# Macro_Duino.net
KiCad netlist of a schematic drawn in EAGLE
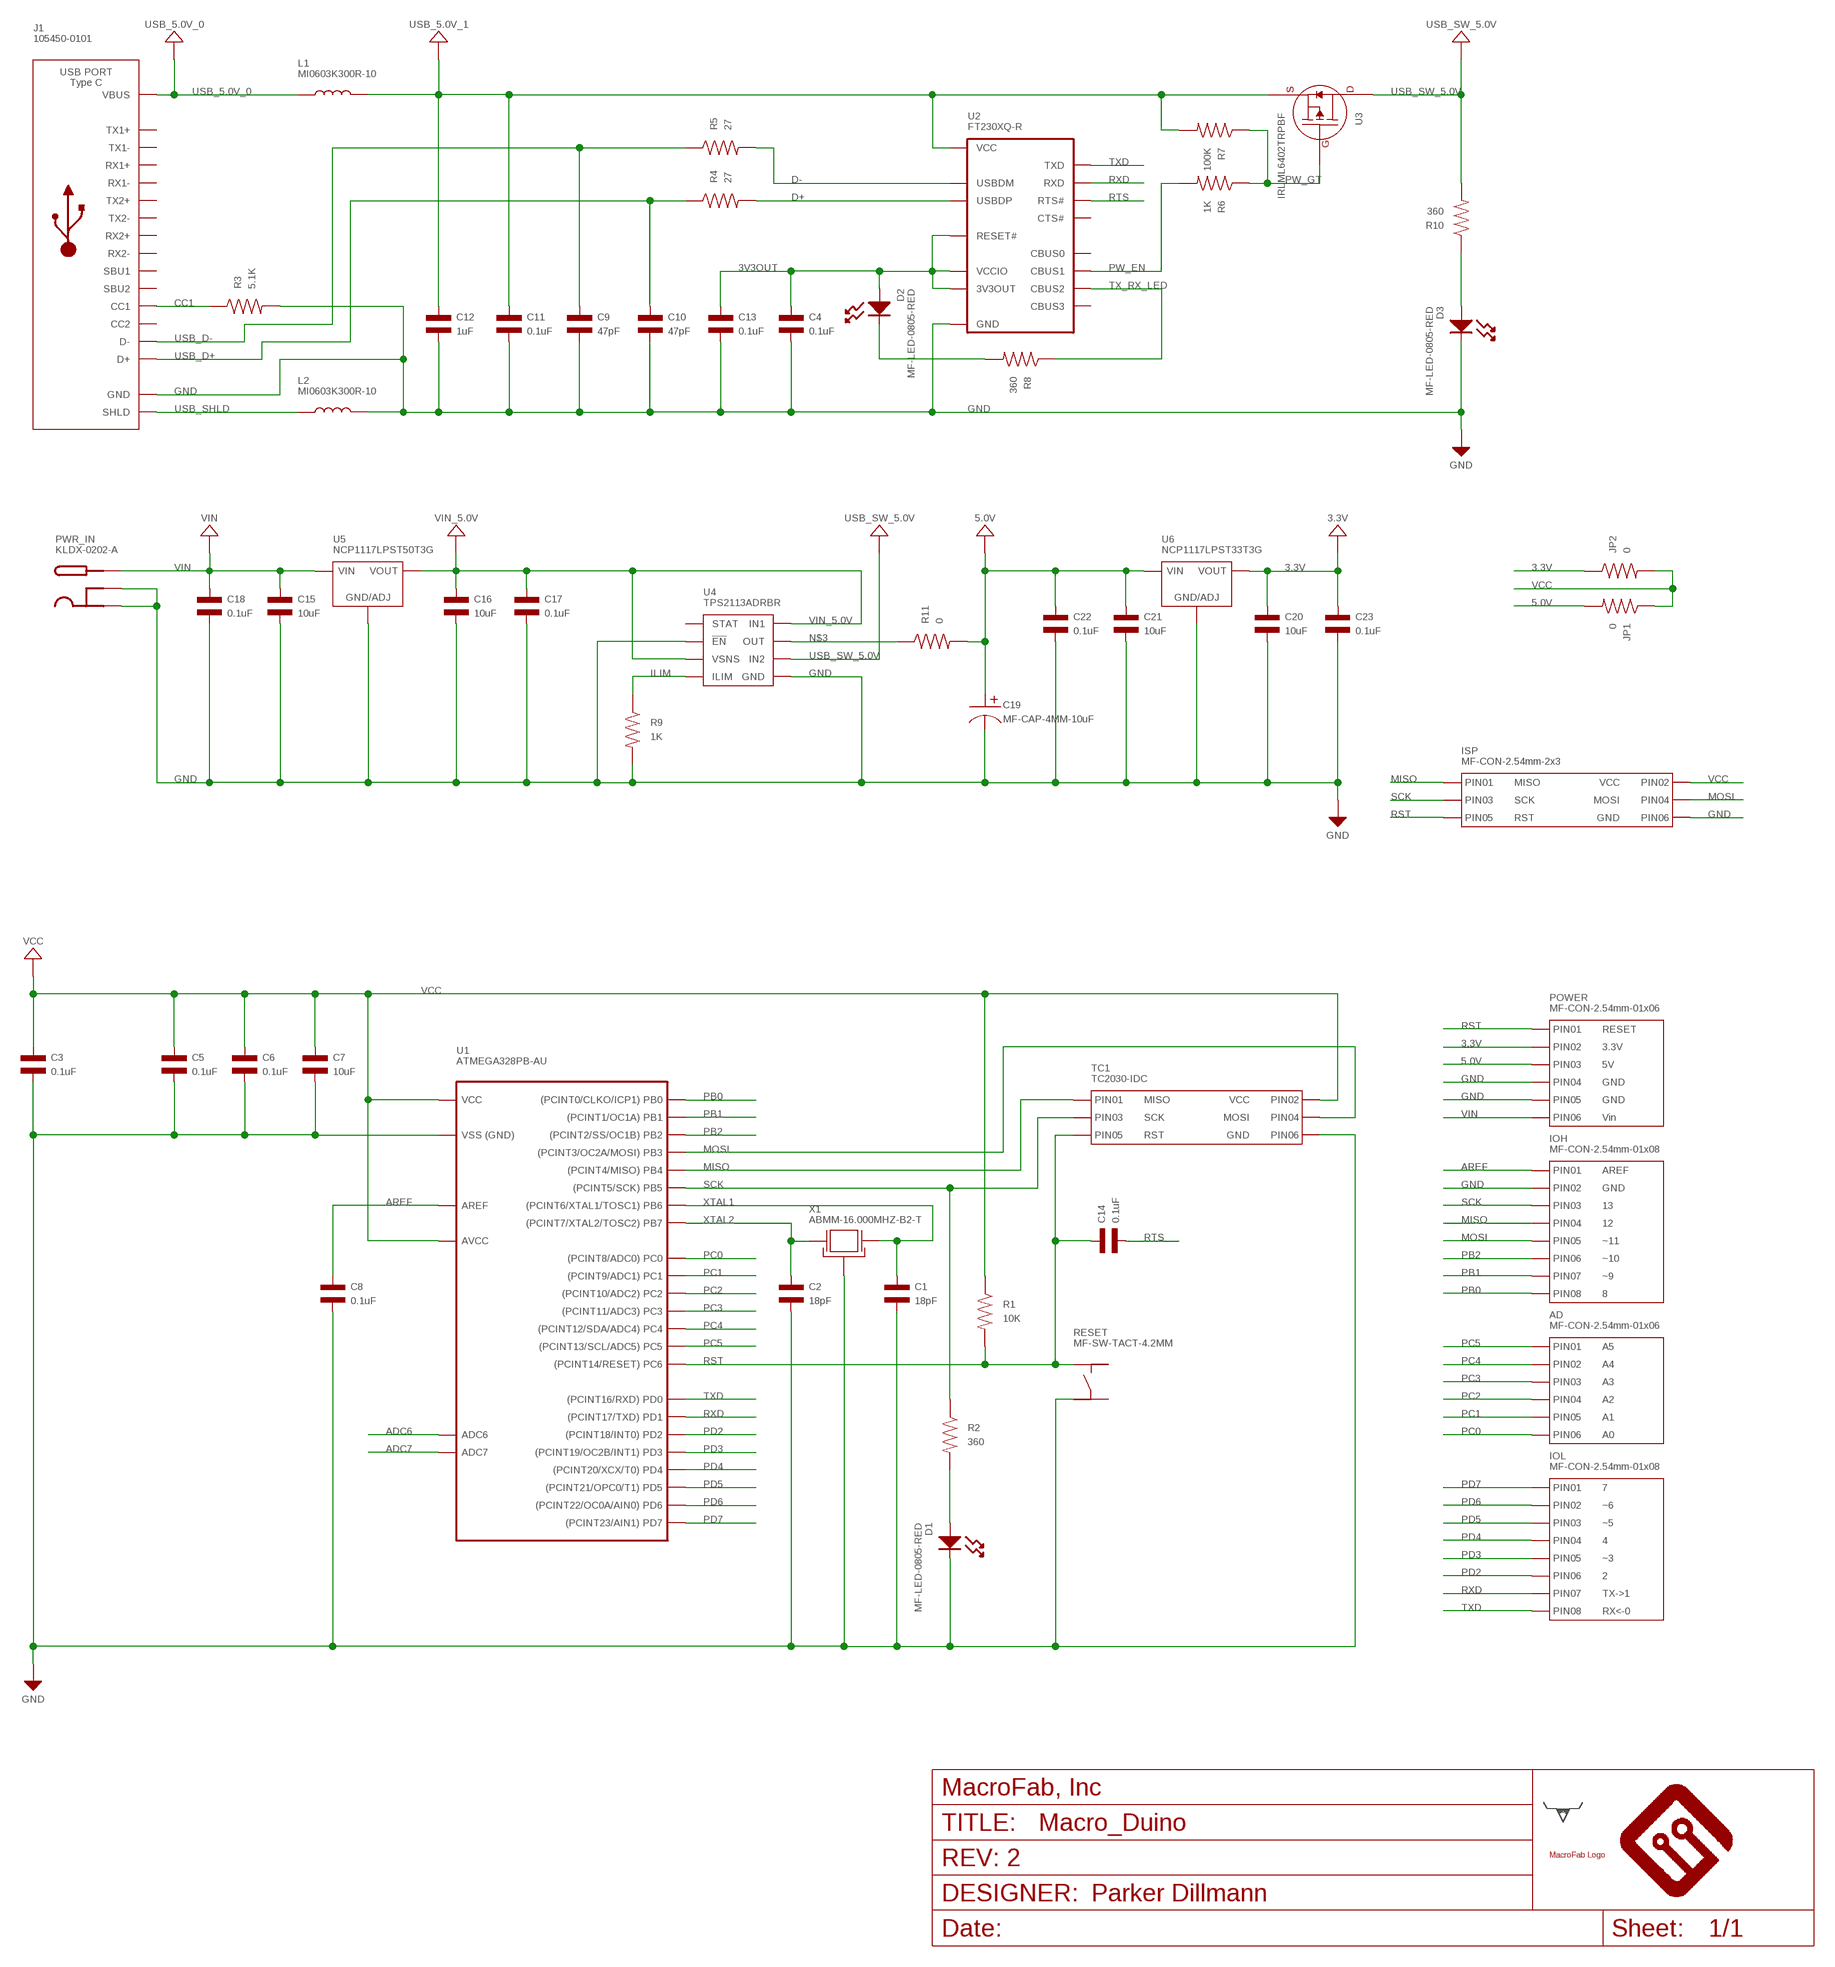
[diagram p0: schematic, sheet 1]

(export (version "E")
  (design (tool "Eeschema 10.0.6"))
  (components
    (comp (ref "AD")
      (value "MF-CON-2.54mm-01x06")
      (footprint "eagle-import:PTH_2.54MM_01X06")
      (fields
        (field (name "HOUSEPART") "YES")
        (field (name "LABEL01") "A5")
        (field (name "LABEL02") "A4")
        (field (name "LABEL03") "A3")
        (field (name "LABEL04") "A2")
        (field (name "LABEL05") "A1")
        (field (name "LABEL06") "A0")
      )
      (libsource (lib "eagle-import") (part "CON_01X06_PTH_2.54MM"))
    )
    (comp (ref "C1")
      (value "18pF")
      (footprint "eagle-import:C0603")
      (fields (field (name "MPN") "VJ0603A180JXACW1BC"))
      (libsource (lib "eagle-import") (part "CAPACITOR_NP_0603"))
    )
    (comp (ref "C2")
      (value "18pF")
      (footprint "eagle-import:C0603")
      (fields (field (name "MPN") "VJ0603A180JXACW1BC"))
      (libsource (lib "eagle-import") (part "CAPACITOR_NP_0603"))
    )
    (comp (ref "C3")
      (value "0.1uF")
      (footprint "eagle-import:C0603")
      (fields (field (name "MPN") "MF-CAP-0603-0.1uF"))
      (libsource (lib "eagle-import") (part "CAPACITOR_NP_0603"))
    )
    (comp (ref "C4")
      (value "0.1uF")
      (footprint "eagle-import:C0603")
      (fields (field (name "MPN") "MF-CAP-0603-0.1uF"))
      (libsource (lib "eagle-import") (part "CAPACITOR_NP_0603"))
    )
    (comp (ref "C5")
      (value "0.1uF")
      (footprint "eagle-import:C0603")
      (fields (field (name "MPN") "MF-CAP-0603-0.1uF"))
      (libsource (lib "eagle-import") (part "CAPACITOR_NP_0603"))
    )
    (comp (ref "C6")
      (value "0.1uF")
      (footprint "eagle-import:C0603")
      (fields (field (name "MPN") "MF-CAP-0603-0.1uF"))
      (libsource (lib "eagle-import") (part "CAPACITOR_NP_0603"))
    )
    (comp (ref "C7")
      (value "10uF")
      (footprint "eagle-import:C1206")
      (fields (field (name "MPN") "MF-CAP-1206-10uF"))
      (libsource (lib "eagle-import") (part "CAPACITOR_NP_1206"))
    )
    (comp (ref "C8")
      (value "0.1uF")
      (footprint "eagle-import:C0603")
      (fields (field (name "MPN") "MF-CAP-0603-0.1uF"))
      (libsource (lib "eagle-import") (part "CAPACITOR_NP_0603"))
    )
    (comp (ref "C9")
      (value "47pF")
      (footprint "eagle-import:C0603")
      (fields (field (name "MPN") "06035A470JAT2A"))
      (libsource (lib "eagle-import") (part "CAPACITOR_NP_0603"))
    )
    (comp (ref "C10")
      (value "47pF")
      (footprint "eagle-import:C0603")
      (fields (field (name "MPN") "06035A470JAT2A"))
      (libsource (lib "eagle-import") (part "CAPACITOR_NP_0603"))
    )
    (comp (ref "C11")
      (value "0.1uF")
      (footprint "eagle-import:C0603")
      (fields (field (name "MPN") "MF-CAP-0603-0.1uF"))
      (libsource (lib "eagle-import") (part "CAPACITOR_NP_0603"))
    )
    (comp (ref "C12")
      (value "1uF")
      (footprint "eagle-import:C0603")
      (fields (field (name "MPN") "MF-CAP-0603-1uF"))
      (libsource (lib "eagle-import") (part "CAPACITOR_NP_0603"))
    )
    (comp (ref "C13")
      (value "0.1uF")
      (footprint "eagle-import:C0603")
      (fields (field (name "MPN") "MF-CAP-0603-0.1uF"))
      (libsource (lib "eagle-import") (part "CAPACITOR_NP_0603"))
    )
    (comp (ref "C14")
      (value "0.1uF")
      (footprint "eagle-import:C0603")
      (fields (field (name "MPN") "MF-CAP-0603-0.1uF"))
      (libsource (lib "eagle-import") (part "CAPACITOR_NP_0603"))
    )
    (comp (ref "C15")
      (value "10uF")
      (footprint "eagle-import:C1206")
      (fields (field (name "MPN") "MF-CAP-1206-10uF"))
      (libsource (lib "eagle-import") (part "CAPACITOR_NP_1206"))
    )
    (comp (ref "C16")
      (value "10uF")
      (footprint "eagle-import:C1206")
      (fields (field (name "MPN") "MF-CAP-1206-10uF"))
      (libsource (lib "eagle-import") (part "CAPACITOR_NP_1206"))
    )
    (comp (ref "C17")
      (value "0.1uF")
      (footprint "eagle-import:C0603")
      (fields (field (name "MPN") "MF-CAP-0603-0.1uF"))
      (libsource (lib "eagle-import") (part "CAPACITOR_NP_0603"))
    )
    (comp (ref "C18")
      (value "0.1uF")
      (footprint "eagle-import:C0603")
      (fields (field (name "MPN") "MF-CAP-0603-0.1uF"))
      (libsource (lib "eagle-import") (part "CAPACITOR_NP_0603"))
    )
    (comp (ref "C19")
      (value "MF-CAP-4MM-10uF")
      (footprint "eagle-import:CP4MM")
      (fields (field (name "MPN") "MF-CAP-4MM-10uF"))
      (libsource (lib "eagle-import") (part "CAPACITOR_P_4MM"))
    )
    (comp (ref "C20")
      (value "10uF")
      (footprint "eagle-import:C1206")
      (fields (field (name "MPN") "MF-CAP-1206-10uF"))
      (libsource (lib "eagle-import") (part "CAPACITOR_NP_1206"))
    )
    (comp (ref "C21")
      (value "10uF")
      (footprint "eagle-import:C1206")
      (fields (field (name "MPN") "MF-CAP-1206-10uF"))
      (libsource (lib "eagle-import") (part "CAPACITOR_NP_1206"))
    )
    (comp (ref "C22")
      (value "0.1uF")
      (footprint "eagle-import:C0603")
      (fields (field (name "MPN") "MF-CAP-0603-0.1uF"))
      (libsource (lib "eagle-import") (part "CAPACITOR_NP_0603"))
    )
    (comp (ref "C23")
      (value "0.1uF")
      (footprint "eagle-import:C0603")
      (fields (field (name "MPN") "MF-CAP-0603-0.1uF"))
      (libsource (lib "eagle-import") (part "CAPACITOR_NP_0603"))
    )
    (comp (ref "D1")
      (value "MF-LED-0805-RED")
      (footprint "eagle-import:LED0805")
      (fields (field (name "HOUSEPART") "YES"))
      (libsource (lib "eagle-import") (part "LED_SINGLE-0805-RED"))
    )
    (comp (ref "D2")
      (value "MF-LED-0805-RED")
      (footprint "eagle-import:LED0805")
      (fields (field (name "HOUSEPART") "YES"))
      (libsource (lib "eagle-import") (part "LED_SINGLE-0805-RED"))
    )
    (comp (ref "D3")
      (value "MF-LED-0805-RED")
      (footprint "eagle-import:LED0805")
      (fields (field (name "HOUSEPART") "YES"))
      (libsource (lib "eagle-import") (part "LED_SINGLE-0805-RED"))
    )
    (comp (ref "FRAME1")
      (value "MF_FRAMEDEFAULT")
      (footprint "eagle-import:MF_FRAME_DEFAULT")
      (fields
        (field (name "HOUSEPART") "0")
        (field (name "DNAME") "Parker Dillmann")
        (field (name "REVNUM") "REV: 2")
      )
      (libsource (lib "eagle-import") (part "MF_FRAMEDEFAULT"))
    )
    (comp (ref "IOH")
      (value "MF-CON-2.54mm-01x08")
      (footprint "eagle-import:PTH_2.54MM_01X08")
      (fields
        (field (name "HOUSEPART") "YES")
        (field (name "LABEL01") "AREF")
        (field (name "LABEL02") "GND")
        (field (name "LABEL03") "13")
        (field (name "LABEL04") "12")
        (field (name "LABEL05") "~11")
        (field (name "LABEL06") "~10")
        (field (name "LABEL07") "~9")
        (field (name "LABEL08") "8")
      )
      (libsource (lib "eagle-import") (part "CON_01X08_PTH_2.54MM"))
    )
    (comp (ref "IOL")
      (value "MF-CON-2.54mm-01x08")
      (footprint "eagle-import:PTH_2.54MM_01X08")
      (fields
        (field (name "HOUSEPART") "YES")
        (field (name "LABEL01") "7")
        (field (name "LABEL02") "~6")
        (field (name "LABEL03") "~5")
        (field (name "LABEL04") "4")
        (field (name "LABEL05") "~3")
        (field (name "LABEL06") "2")
        (field (name "LABEL07") "TX->1")
        (field (name "LABEL08") "RX<-0")
      )
      (libsource (lib "eagle-import") (part "CON_01X08_PTH_2.54MM"))
    )
    (comp (ref "ISP")
      (value "MF-CON-2.54mm-2x3")
      (footprint "eagle-import:PTH_2.54MM_02X03")
      (fields
        (field (name "HOUSEPART") "YES")
        (field (name "LABEL01") "MISO")
        (field (name "LABEL02") "VCC")
        (field (name "LABEL03") "SCK")
        (field (name "LABEL04") "MOSI")
        (field (name "LABEL05") "RST")
        (field (name "LABEL06") "GND")
      )
      (libsource (lib "eagle-import") (part "CON_02X03_PTH_2.54MM"))
    )
    (comp (ref "J1")
      (value "105450-0101")
      (footprint "eagle-import:105450-0101")
      (fields (field (name "MPN") "105450-0101"))
      (libsource (lib "eagle-import") (part "USB_TYPE-C_105450-0101"))
    )
    (comp (ref "JP1")
      (value "0")
      (footprint "eagle-import:R0805")
      (fields (field (name "MPN") "MF-RES-0805-0"))
      (libsource (lib "eagle-import") (part "RESISTOR_0805"))
    )
    (comp (ref "JP2")
      (value "0")
      (footprint "eagle-import:R0805")
      (fields (field (name "MPN") "MF-RES-0805-0") (field (name "POPULATE") "0"))
      (libsource (lib "eagle-import") (part "RESISTOR_0805"))
    )
    (comp (ref "L1")
      (value "MI0603K300R-10")
      (footprint "eagle-import:L0603")
      (fields (field (name "MPN") "MI0603K300R-10"))
      (libsource (lib "eagle-import") (part "INDUCTOR_0603"))
    )
    (comp (ref "L2")
      (value "MI0603K300R-10")
      (footprint "eagle-import:L0603")
      (fields (field (name "MPN") "MI0603K300R-10"))
      (libsource (lib "eagle-import") (part "INDUCTOR_0603"))
    )
    (comp (ref "POWER")
      (value "MF-CON-2.54mm-01x06")
      (footprint "eagle-import:PTH_2.54MM_01X06")
      (fields
        (field (name "HOUSEPART") "YES")
        (field (name "LABEL01") "RESET")
        (field (name "LABEL02") "3.3V")
        (field (name "LABEL03") "5V")
        (field (name "LABEL04") "GND")
        (field (name "LABEL05") "GND")
        (field (name "LABEL06") "Vin")
      )
      (libsource (lib "eagle-import") (part "CON_01X06_PTH_2.54MM"))
    )
    (comp (ref "PWR_IN")
      (value "KLDX-0202-A")
      (footprint "eagle-import:DC_PWR_JACK")
      (fields (field (name "HOUSEPART") "NO"))
      (libsource (lib "eagle-import") (part "DC_PWR_JACK_2.0MM_RIGHT"))
    )
    (comp (ref "R1")
      (value "10K")
      (footprint "eagle-import:R0603")
      (fields (field (name "MPN") "MF-RES-0603-10K"))
      (libsource (lib "eagle-import") (part "RESISTOR_0603"))
    )
    (comp (ref "R2")
      (value "360")
      (footprint "eagle-import:R0603")
      (fields (field (name "MPN") "MF-RES-0603-360"))
      (libsource (lib "eagle-import") (part "RESISTOR_0603"))
    )
    (comp (ref "R3")
      (value "5.1K")
      (footprint "eagle-import:R0603")
      (fields (field (name "MPN") "CR0603-FX-5101ELF"))
      (libsource (lib "eagle-import") (part "RESISTOR_0603"))
    )
    (comp (ref "R4")
      (value "27")
      (footprint "eagle-import:R0603")
      (fields (field (name "MPN") "MF-RES-0603-27"))
      (libsource (lib "eagle-import") (part "RESISTOR_0603"))
    )
    (comp (ref "R5")
      (value "27")
      (footprint "eagle-import:R0603")
      (fields (field (name "MPN") "MF-RES-0603-27"))
      (libsource (lib "eagle-import") (part "RESISTOR_0603"))
    )
    (comp (ref "R6")
      (value "1K")
      (footprint "eagle-import:R0603")
      (fields (field (name "MPN") "MF-RES-0603-1K"))
      (libsource (lib "eagle-import") (part "RESISTOR_0603"))
    )
    (comp (ref "R7")
      (value "100K")
      (footprint "eagle-import:R0603")
      (fields (field (name "MPN") "MF-RES-0603-100K"))
      (libsource (lib "eagle-import") (part "RESISTOR_0603"))
    )
    (comp (ref "R8")
      (value "360")
      (footprint "eagle-import:R0603")
      (fields (field (name "MPN") "MF-RES-0603-360"))
      (libsource (lib "eagle-import") (part "RESISTOR_0603"))
    )
    (comp (ref "R9")
      (value "1K")
      (footprint "eagle-import:R0603")
      (fields (field (name "MPN") "MF-RES-0603-1K"))
      (libsource (lib "eagle-import") (part "RESISTOR_0603"))
    )
    (comp (ref "R10")
      (value "360")
      (footprint "eagle-import:R0603")
      (fields (field (name "MPN") "MF-RES-0603-360"))
      (libsource (lib "eagle-import") (part "RESISTOR_0603"))
    )
    (comp (ref "R11")
      (value "0")
      (footprint "eagle-import:R0805")
      (fields (field (name "MPN") "MF-RES-0805-0"))
      (libsource (lib "eagle-import") (part "RESISTOR_0805"))
    )
    (comp (ref "RESET")
      (value "MF-SW-TACT-4.2MM")
      (footprint "eagle-import:TACT4.2MM")
      (fields (field (name "HOUSEPART") "YES"))
      (libsource (lib "eagle-import") (part "TACT_4.2MM"))
    )
    (comp (ref "TC1")
      (value "TC2030-IDC")
      (footprint "eagle-import:TC2030-IDC-FP")
      (fields (field (name "HOUSEPART") "NO"))
      (libsource (lib "eagle-import") (part "CON_02X03_TC2030-IDC_AVRISP"))
    )
    (comp (ref "U$14")
      (value "MF_LOGOLOGO")
      (footprint "eagle-import:MF_LOGO")
      (libsource (lib "eagle-import") (part "MF_LOGOLOGO"))
    )
    (comp (ref "U$15")
      (value "LHE_LOGOLHE_LOGO")
      (footprint "eagle-import:LHE_LOGO")
      (libsource (lib "eagle-import") (part "LHE_LOGOLHE_LOGO"))
    )
    (comp (ref "U1")
      (value "ATMEGA328PB-AU")
      (footprint "eagle-import:TQFP32")
      (fields
        (field (name "HOUSEPART") "NO")
        (field (name "MPN") "ATMEGA328P-AU")
        (field (name "MPN_1") "ATMEGA328PB-AU ")
      )
      (libsource (lib "eagle-import") (part "ATMEGA328P-AU"))
    )
    (comp (ref "U2")
      (value "FT230XQ-R")
      (footprint "eagle-import:FT230X_QFN-16")
      (libsource (lib "eagle-import") (part "FT230XQ"))
    )
    (comp (ref "U3")
      (value "IRLML6402TRPBF")
      (footprint "eagle-import:SOT-23-3")
      (libsource (lib "eagle-import") (part "MOSFET_P-CHANNEL_SINGLE_SOT-23"))
    )
    (comp (ref "U4")
      (value "TPS2113ADRBR")
      (footprint "eagle-import:TPS211X_SON-8")
      (libsource (lib "eagle-import") (part "TPS211(2/3)ADR"))
    )
    (comp (ref "U5")
      (value "NCP1117LPST50T3G")
      (footprint "eagle-import:SOT-223-3")
      (fields (field (name "HOUSEPART") "NO"))
      (libsource (lib "eagle-import") (part "NCP1117LPST50T3G"))
    )
    (comp (ref "U6")
      (value "NCP1117LPST33T3G")
      (footprint "eagle-import:SOT-223-3")
      (fields (field (name "HOUSEPART") "NO"))
      (libsource (lib "eagle-import") (part "NCP1117LPST33T3G"))
    )
    (comp (ref "X1")
      (value "ABMM-16.000MHZ-B2-T")
      (footprint "eagle-import:7MMX5MM")
      (fields (field (name "HOUSEPART") "NO") (field (name "MPN") "ABMM-16.000MHZ-B2-T"))
      (libsource (lib "eagle-import") (part "CYRSTAL_GND_ABMM"))
    )
  )
  (nets
    (net (code "1") (name "/3V3OUT") (class "Default")
      (node (ref "C13") (pin "P$1") (pinfunction "P$1_P$1") (pintype "passive"))
      (node (ref "C4") (pin "P$1") (pinfunction "P$1_P$1") (pintype "passive"))
      (node (ref "D2") (pin "ANODE") (pinfunction "ANODE_ANODE") (pintype "power_in"))
      (node (ref "U2") (pin "1") (pinfunction "VCCIO_1") (pintype "bidirectional"))
      (node (ref "U2") (pin "8") (pinfunction "3V3OUT_8") (pintype "bidirectional"))
      (node (ref "U2") (pin "9") (pinfunction "RESET#_9") (pintype "bidirectional"))
    )
    (net (code "2") (name "/ADC6") (class "Default")
      (node (ref "U1") (pin "P$19") (pinfunction "ADC6_P$19") (pintype "bidirectional"))
    )
    (net (code "3") (name "/ADC7") (class "Default")
      (node (ref "U1") (pin "P$22") (pinfunction "ADC7_P$22") (pintype "bidirectional"))
    )
    (net (code "4") (name "/AREF") (class "Default")
      (node (ref "C8") (pin "P$1") (pinfunction "P$1_P$1") (pintype "passive"))
      (node (ref "IOH") (pin "P$1") (pinfunction "PIN1_P$1") (pintype "bidirectional"))
      (node (ref "U1") (pin "P$20") (pinfunction "AREF_P$20") (pintype "power_in"))
    )
    (net (code "5") (name "/CC1") (class "Default")
      (node (ref "J1") (pin "A5") (pinfunction "CC1_A5") (pintype "bidirectional"))
      (node (ref "R3") (pin "P$1") (pinfunction "P$1_P$1") (pintype "passive"))
    )
    (net (code "6") (name "/D+") (class "Default")
      (node (ref "R4") (pin "P$2") (pinfunction "P$2_P$2") (pintype "passive"))
      (node (ref "U2") (pin "6") (pinfunction "USBDP_6") (pintype "bidirectional"))
    )
    (net (code "7") (name "/D-") (class "Default")
      (node (ref "R5") (pin "P$2") (pinfunction "P$2_P$2") (pintype "passive"))
      (node (ref "U2") (pin "7") (pinfunction "USBDM_7") (pintype "bidirectional"))
    )
    (net (code "8") (name "/ILIM") (class "Default")
      (node (ref "R9") (pin "P$1") (pinfunction "P$1_P$1") (pintype "passive"))
      (node (ref "U4") (pin "4") (pinfunction "ILIM_4") (pintype "bidirectional"))
    )
    (net (code "9") (name "/MISO") (class "Default")
      (node (ref "IOH") (pin "P$4") (pinfunction "PIN4_P$4") (pintype "bidirectional"))
      (node (ref "ISP") (pin "P$1") (pinfunction "PIN1_P$1") (pintype "bidirectional"))
      (node (ref "TC1") (pin "P$1") (pinfunction "PIN1_P$1") (pintype "bidirectional"))
      (node (ref "U1") (pin "P$16") (pinfunction "PB4_P$16") (pintype "bidirectional"))
    )
    (net (code "10") (name "/MOSI") (class "Default")
      (node (ref "IOH") (pin "P$5") (pinfunction "PIN5_P$5") (pintype "bidirectional"))
      (node (ref "ISP") (pin "P$4") (pinfunction "PIN4_P$4") (pintype "bidirectional"))
      (node (ref "TC1") (pin "P$4") (pinfunction "PIN4_P$4") (pintype "bidirectional"))
      (node (ref "U1") (pin "P$15") (pinfunction "PB3_P$15") (pintype "bidirectional"))
    )
    (net (code "11") (name "/N$3") (class "Default")
      (node (ref "R11") (pin "P$1") (pinfunction "P$1_P$1") (pintype "passive"))
      (node (ref "U4") (pin "7") (pinfunction "OUT_7") (pintype "bidirectional"))
    )
    (net (code "12") (name "/PB0") (class "Default")
      (node (ref "IOH") (pin "P$8") (pinfunction "PIN8_P$8") (pintype "bidirectional"))
      (node (ref "U1") (pin "P$12") (pinfunction "PB0_P$12") (pintype "bidirectional"))
    )
    (net (code "13") (name "/PB1") (class "Default")
      (node (ref "IOH") (pin "P$7") (pinfunction "PIN7_P$7") (pintype "bidirectional"))
      (node (ref "U1") (pin "P$13") (pinfunction "PB1_P$13") (pintype "bidirectional"))
    )
    (net (code "14") (name "/PB2") (class "Default")
      (node (ref "IOH") (pin "P$6") (pinfunction "PIN6_P$6") (pintype "bidirectional"))
      (node (ref "U1") (pin "P$14") (pinfunction "PB2_P$14") (pintype "bidirectional"))
    )
    (net (code "15") (name "/PC0") (class "Default")
      (node (ref "AD") (pin "P$6") (pinfunction "PIN6_P$6") (pintype "bidirectional"))
      (node (ref "U1") (pin "P$23") (pinfunction "PC0_P$23") (pintype "bidirectional"))
    )
    (net (code "16") (name "/PC1") (class "Default")
      (node (ref "AD") (pin "P$5") (pinfunction "PIN5_P$5") (pintype "bidirectional"))
      (node (ref "U1") (pin "P$24") (pinfunction "PC1_P$24") (pintype "bidirectional"))
    )
    (net (code "17") (name "/PC2") (class "Default")
      (node (ref "AD") (pin "P$4") (pinfunction "PIN4_P$4") (pintype "bidirectional"))
      (node (ref "U1") (pin "P$25") (pinfunction "PC2_P$25") (pintype "bidirectional"))
    )
    (net (code "18") (name "/PC3") (class "Default")
      (node (ref "AD") (pin "P$3") (pinfunction "PIN3_P$3") (pintype "bidirectional"))
      (node (ref "U1") (pin "P$26") (pinfunction "PC3_P$26") (pintype "bidirectional"))
    )
    (net (code "19") (name "/PC4") (class "Default")
      (node (ref "AD") (pin "P$2") (pinfunction "PIN2_P$2") (pintype "bidirectional"))
      (node (ref "U1") (pin "P$27") (pinfunction "PC4_P$27") (pintype "bidirectional"))
    )
    (net (code "20") (name "/PC5") (class "Default")
      (node (ref "AD") (pin "P$1") (pinfunction "PIN1_P$1") (pintype "bidirectional"))
      (node (ref "U1") (pin "P$28") (pinfunction "PC5_P$28") (pintype "bidirectional"))
    )
    (net (code "21") (name "/PD2") (class "Default")
      (node (ref "IOL") (pin "P$6") (pinfunction "PIN6_P$6") (pintype "bidirectional"))
      (node (ref "U1") (pin "P$32") (pinfunction "PD2_P$32") (pintype "bidirectional"))
    )
    (net (code "22") (name "/PD3") (class "Default")
      (node (ref "IOL") (pin "P$5") (pinfunction "PIN5_P$5") (pintype "bidirectional"))
      (node (ref "U1") (pin "P$1") (pinfunction "PD3_P$1") (pintype "bidirectional"))
    )
    (net (code "23") (name "/PD4") (class "Default")
      (node (ref "IOL") (pin "P$4") (pinfunction "PIN4_P$4") (pintype "bidirectional"))
      (node (ref "U1") (pin "P$2") (pinfunction "PD4_P$2") (pintype "bidirectional"))
    )
    (net (code "24") (name "/PD5") (class "Default")
      (node (ref "IOL") (pin "P$3") (pinfunction "PIN3_P$3") (pintype "bidirectional"))
      (node (ref "U1") (pin "P$9") (pinfunction "PD5_P$9") (pintype "bidirectional"))
    )
    (net (code "25") (name "/PD6") (class "Default")
      (node (ref "IOL") (pin "P$2") (pinfunction "PIN2_P$2") (pintype "bidirectional"))
      (node (ref "U1") (pin "P$10") (pinfunction "PD6_P$10") (pintype "bidirectional"))
    )
    (net (code "26") (name "/PD7") (class "Default")
      (node (ref "IOL") (pin "P$1") (pinfunction "PIN1_P$1") (pintype "bidirectional"))
      (node (ref "U1") (pin "P$11") (pinfunction "PD7_P$11") (pintype "bidirectional"))
    )
    (net (code "27") (name "/PW_EN") (class "Default")
      (node (ref "R6") (pin "P$2") (pinfunction "P$2_P$2") (pintype "passive"))
      (node (ref "U2") (pin "11") (pinfunction "CBUS1_11") (pintype "bidirectional"))
    )
    (net (code "28") (name "/PW_GT") (class "Default")
      (node (ref "R6") (pin "P$1") (pinfunction "P$1_P$1") (pintype "passive"))
      (node (ref "R7") (pin "P$1") (pinfunction "P$1_P$1") (pintype "passive"))
      (node (ref "U3") (pin "1") (pinfunction "GATE_1") (pintype "bidirectional"))
    )
    (net (code "29") (name "/RST") (class "Default")
      (node (ref "C14") (pin "P$1") (pinfunction "P$1_P$1") (pintype "passive"))
      (node (ref "ISP") (pin "P$5") (pinfunction "PIN5_P$5") (pintype "bidirectional"))
      (node (ref "POWER") (pin "P$1") (pinfunction "PIN1_P$1") (pintype "bidirectional"))
      (node (ref "R1") (pin "P$2") (pinfunction "P$2_P$2") (pintype "passive"))
      (node (ref "RESET") (pin "P$1") (pinfunction "P$1_P$1") (pintype "bidirectional"))
      (node (ref "TC1") (pin "P$5") (pinfunction "PIN5_P$5") (pintype "bidirectional"))
      (node (ref "U1") (pin "P$29") (pinfunction "PC6_P$29") (pintype "bidirectional"))
    )
    (net (code "30") (name "/RTS") (class "Default")
      (node (ref "C14") (pin "P$2") (pinfunction "P$2_P$2") (pintype "passive"))
      (node (ref "U2") (pin "16") (pinfunction "RTS#_16") (pintype "bidirectional"))
    )
    (net (code "31") (name "/RXD") (class "Default")
      (node (ref "IOL") (pin "P$7") (pinfunction "PIN7_P$7") (pintype "bidirectional"))
      (node (ref "U1") (pin "P$31") (pinfunction "PD1_P$31") (pintype "bidirectional"))
      (node (ref "U2") (pin "2") (pinfunction "RXD_2") (pintype "bidirectional"))
    )
    (net (code "32") (name "/SCK") (class "Default")
      (node (ref "IOH") (pin "P$3") (pinfunction "PIN3_P$3") (pintype "bidirectional"))
      (node (ref "ISP") (pin "P$3") (pinfunction "PIN3_P$3") (pintype "bidirectional"))
      (node (ref "R2") (pin "P$1") (pinfunction "P$1_P$1") (pintype "passive"))
      (node (ref "TC1") (pin "P$3") (pinfunction "PIN3_P$3") (pintype "bidirectional"))
      (node (ref "U1") (pin "P$17") (pinfunction "PB5_P$17") (pintype "bidirectional"))
    )
    (net (code "33") (name "/TXD") (class "Default")
      (node (ref "IOL") (pin "P$8") (pinfunction "PIN8_P$8") (pintype "bidirectional"))
      (node (ref "U1") (pin "P$30") (pinfunction "PD0_P$30") (pintype "bidirectional"))
      (node (ref "U2") (pin "15") (pinfunction "TXD_15") (pintype "bidirectional"))
    )
    (net (code "34") (name "/TX_RX_LED") (class "Default")
      (node (ref "R8") (pin "P$1") (pinfunction "P$1_P$1") (pintype "passive"))
      (node (ref "U2") (pin "5") (pinfunction "CBUS2_5") (pintype "bidirectional"))
    )
    (net (code "35") (name "/USB_D+") (class "Default")
      (node (ref "C10") (pin "P$1") (pinfunction "P$1_P$1") (pintype "passive"))
      (node (ref "J1") (pin "A6") (pinfunction "D+_A6") (pintype "bidirectional"))
      (node (ref "J1") (pin "B6") (pinfunction "D+_B6") (pintype "bidirectional"))
      (node (ref "R4") (pin "P$1") (pinfunction "P$1_P$1") (pintype "passive"))
    )
    (net (code "36") (name "/USB_D-") (class "Default")
      (node (ref "C9") (pin "P$1") (pinfunction "P$1_P$1") (pintype "passive"))
      (node (ref "J1") (pin "A7") (pinfunction "D-_A7") (pintype "bidirectional"))
      (node (ref "J1") (pin "B7") (pinfunction "D-_B7") (pintype "bidirectional"))
      (node (ref "R5") (pin "P$1") (pinfunction "P$1_P$1") (pintype "passive"))
    )
    (net (code "37") (name "/USB_SHLD") (class "Default")
      (node (ref "J1") (pin "S_T1") (pinfunction "SHLD_S_T1") (pintype "bidirectional"))
      (node (ref "J1") (pin "S_T2") (pinfunction "SHLD_S_T2") (pintype "bidirectional"))
      (node (ref "J1") (pin "S_T3") (pinfunction "SHLD_S_T3") (pintype "bidirectional"))
      (node (ref "J1") (pin "S_T4") (pinfunction "SHLD_S_T4") (pintype "bidirectional"))
      (node (ref "L2") (pin "P$1") (pinfunction "P$1_P$1") (pintype "passive"))
    )
    (net (code "38") (name "/XTAL1") (class "Default")
      (node (ref "C1") (pin "P$1") (pinfunction "P$1_P$1") (pintype "passive"))
      (node (ref "U1") (pin "P$7") (pinfunction "PB6_P$7") (pintype "bidirectional"))
      (node (ref "X1") (pin "P$3") (pinfunction "X1_P$3") (pintype "bidirectional"))
    )
    (net (code "39") (name "/XTAL2") (class "Default")
      (node (ref "C2") (pin "P$1") (pinfunction "P$1_P$1") (pintype "passive"))
      (node (ref "U1") (pin "P$8") (pinfunction "PB7_P$8") (pintype "bidirectional"))
      (node (ref "X1") (pin "P$1") (pinfunction "X0_P$1") (pintype "bidirectional"))
    )
    (net (code "40") (name "3.3V") (class "Default")
      (node (ref "C20") (pin "P$1") (pinfunction "P$1_P$1") (pintype "passive"))
      (node (ref "C23") (pin "P$1") (pinfunction "P$1_P$1") (pintype "passive"))
      (node (ref "JP2") (pin "P$1") (pinfunction "P$1_P$1") (pintype "passive"))
      (node (ref "POWER") (pin "P$2") (pinfunction "PIN2_P$2") (pintype "bidirectional"))
      (node (ref "U6") (pin "P$1") (pinfunction "VOUT_P$1") (pintype "bidirectional"))
      (node (ref "U6") (pin "P$3") (pinfunction "VOUT_P$3") (pintype "bidirectional"))
    )
    (net (code "41") (name "5.0V") (class "Default")
      (node (ref "C19") (pin "P$1") (pinfunction "P$1_P$1") (pintype "passive"))
      (node (ref "C21") (pin "P$1") (pinfunction "P$1_P$1") (pintype "passive"))
      (node (ref "C22") (pin "P$1") (pinfunction "P$1_P$1") (pintype "passive"))
      (node (ref "JP1") (pin "P$2") (pinfunction "P$2_P$2") (pintype "passive"))
      (node (ref "POWER") (pin "P$3") (pinfunction "PIN3_P$3") (pintype "bidirectional"))
      (node (ref "R11") (pin "P$2") (pinfunction "P$2_P$2") (pintype "passive"))
      (node (ref "U6") (pin "P$4") (pinfunction "VIN_P$4") (pintype "bidirectional"))
    )
    (net (code "42") (name "GND") (class "Default")
      (node (ref "C1") (pin "P$2") (pinfunction "P$2_P$2") (pintype "passive"))
      (node (ref "C10") (pin "P$2") (pinfunction "P$2_P$2") (pintype "passive"))
      (node (ref "C11") (pin "P$2") (pinfunction "P$2_P$2") (pintype "passive"))
      (node (ref "C12") (pin "P$2") (pinfunction "P$2_P$2") (pintype "passive"))
      (node (ref "C13") (pin "P$2") (pinfunction "P$2_P$2") (pintype "passive"))
      (node (ref "C15") (pin "P$2") (pinfunction "P$2_P$2") (pintype "passive"))
      (node (ref "C16") (pin "P$2") (pinfunction "P$2_P$2") (pintype "passive"))
      (node (ref "C17") (pin "P$2") (pinfunction "P$2_P$2") (pintype "passive"))
      (node (ref "C18") (pin "P$2") (pinfunction "P$2_P$2") (pintype "passive"))
      (node (ref "C19") (pin "P$2") (pinfunction "P$2_P$2") (pintype "passive"))
      (node (ref "C2") (pin "P$2") (pinfunction "P$2_P$2") (pintype "passive"))
      (node (ref "C20") (pin "P$2") (pinfunction "P$2_P$2") (pintype "passive"))
      (node (ref "C21") (pin "P$2") (pinfunction "P$2_P$2") (pintype "passive"))
      (node (ref "C22") (pin "P$2") (pinfunction "P$2_P$2") (pintype "passive"))
      (node (ref "C23") (pin "P$2") (pinfunction "P$2_P$2") (pintype "passive"))
      (node (ref "C3") (pin "P$2") (pinfunction "P$2_P$2") (pintype "passive"))
      (node (ref "C4") (pin "P$2") (pinfunction "P$2_P$2") (pintype "passive"))
      (node (ref "C5") (pin "P$2") (pinfunction "P$2_P$2") (pintype "passive"))
      (node (ref "C6") (pin "P$2") (pinfunction "P$2_P$2") (pintype "passive"))
      (node (ref "C7") (pin "P$2") (pinfunction "P$2_P$2") (pintype "passive"))
      (node (ref "C8") (pin "P$2") (pinfunction "P$2_P$2") (pintype "passive"))
      (node (ref "C9") (pin "P$2") (pinfunction "P$2_P$2") (pintype "passive"))
      (node (ref "D1") (pin "CATHODE") (pinfunction "CATHODE_CATHODE") (pintype "power_in"))
      (node (ref "D3") (pin "CATHODE") (pinfunction "CATHODE_CATHODE") (pintype "power_in"))
      (node (ref "IOH") (pin "P$2") (pinfunction "PIN2_P$2") (pintype "bidirectional"))
      (node (ref "ISP") (pin "P$6") (pinfunction "PIN6_P$6") (pintype "bidirectional"))
      (node (ref "J1") (pin "A1") (pinfunction "GND_A1") (pintype "bidirectional"))
      (node (ref "J1") (pin "A12") (pinfunction "GND_A12") (pintype "bidirectional"))
      (node (ref "J1") (pin "B1") (pinfunction "GND_B1") (pintype "bidirectional"))
      (node (ref "J1") (pin "B12") (pinfunction "GND_B12") (pintype "bidirectional"))
      (node (ref "L2") (pin "P$2") (pinfunction "P$2_P$2") (pintype "passive"))
      (node (ref "POWER") (pin "P$4") (pinfunction "PIN4_P$4") (pintype "bidirectional"))
      (node (ref "POWER") (pin "P$5") (pinfunction "PIN5_P$5") (pintype "bidirectional"))
      (node (ref "PWR_IN") (pin "SLEEVE1") (pinfunction "SLEEVE_SLEEVE1") (pintype "power_in"))
      (node (ref "PWR_IN") (pin "SLEEVE2") (pinfunction "SLEEVE_SHUNT_SLEEVE2") (pintype "power_in"))
      (node (ref "R3") (pin "P$2") (pinfunction "P$2_P$2") (pintype "passive"))
      (node (ref "R9") (pin "P$2") (pinfunction "P$2_P$2") (pintype "passive"))
      (node (ref "RESET") (pin "P$3") (pinfunction "P$3_P$3") (pintype "bidirectional"))
      (node (ref "TC1") (pin "P$6") (pinfunction "PIN6_P$6") (pintype "bidirectional"))
      (node (ref "U1") (pin "P$21") (pinfunction "GND_P$21") (pintype "power_in"))
      (node (ref "U1") (pin "P$3") (pinfunction "GND_P$3") (pintype "power_in"))
      (node (ref "U1") (pin "P$5") (pinfunction "GND_P$5") (pintype "power_in"))
      (node (ref "U2") (pin "13") (pinfunction "GND_13") (pintype "bidirectional"))
      (node (ref "U2") (pin "3") (pinfunction "GND_3") (pintype "bidirectional"))
      (node (ref "U2") (pin "PAD") (pinfunction "GND_PAD") (pintype "bidirectional"))
      (node (ref "U4") (pin "2") (pinfunction "~{EN}_2") (pintype "bidirectional"))
      (node (ref "U4") (pin "5") (pinfunction "GND_5") (pintype "bidirectional"))
      (node (ref "U4") (pin "PAD") (pinfunction "GND_PAD") (pintype "bidirectional"))
      (node (ref "U5") (pin "P$2") (pinfunction "GND/ADJ_P$2") (pintype "bidirectional"))
      (node (ref "U6") (pin "P$2") (pinfunction "GND/ADJ_P$2") (pintype "bidirectional"))
      (node (ref "X1") (pin "P$2") (pinfunction "GND_P$2") (pintype "bidirectional"))
      (node (ref "X1") (pin "P$4") (pinfunction "GND_P$4") (pintype "bidirectional"))
    )
    (net (code "43") (name "Net-(D1-PadANODE)") (class "Default")
      (node (ref "D1") (pin "ANODE") (pinfunction "ANODE_ANODE") (pintype "power_in"))
      (node (ref "R2") (pin "P$2") (pinfunction "P$2_P$2") (pintype "passive"))
    )
    (net (code "44") (name "Net-(D2-PadCATHODE)") (class "Default")
      (node (ref "D2") (pin "CATHODE") (pinfunction "CATHODE_CATHODE") (pintype "power_in"))
      (node (ref "R8") (pin "P$2") (pinfunction "P$2_P$2") (pintype "passive"))
    )
    (net (code "45") (name "Net-(D3-PadANODE)") (class "Default")
      (node (ref "D3") (pin "ANODE") (pinfunction "ANODE_ANODE") (pintype "power_in"))
      (node (ref "R10") (pin "P$1") (pinfunction "P$1_P$1") (pintype "passive"))
    )
    (net (code "46") (name "USB_5.0V_0") (class "Default")
      (node (ref "J1") (pin "A4") (pinfunction "VBUS_A4") (pintype "bidirectional"))
      (node (ref "J1") (pin "A9") (pinfunction "VBUS_A9") (pintype "bidirectional"))
      (node (ref "J1") (pin "B4") (pinfunction "VBUS_B4") (pintype "bidirectional"))
      (node (ref "J1") (pin "B9") (pinfunction "VBUS_B9") (pintype "bidirectional"))
      (node (ref "L1") (pin "P$1") (pinfunction "P$1_P$1") (pintype "passive"))
    )
    (net (code "47") (name "USB_5.0V_1") (class "Default")
      (node (ref "C11") (pin "P$1") (pinfunction "P$1_P$1") (pintype "passive"))
      (node (ref "C12") (pin "P$1") (pinfunction "P$1_P$1") (pintype "passive"))
      (node (ref "L1") (pin "P$2") (pinfunction "P$2_P$2") (pintype "passive"))
      (node (ref "R7") (pin "P$2") (pinfunction "P$2_P$2") (pintype "passive"))
      (node (ref "U2") (pin "10") (pinfunction "VCC_10") (pintype "bidirectional"))
      (node (ref "U3") (pin "2") (pinfunction "SOURCE_2") (pintype "bidirectional"))
    )
    (net (code "48") (name "USB_SW_5.0V") (class "Default")
      (node (ref "R10") (pin "P$2") (pinfunction "P$2_P$2") (pintype "passive"))
      (node (ref "U3") (pin "3") (pinfunction "DRAIN_3") (pintype "bidirectional"))
      (node (ref "U4") (pin "6") (pinfunction "IN2_6") (pintype "bidirectional"))
    )
    (net (code "49") (name "VCC") (class "Default")
      (node (ref "C3") (pin "P$1") (pinfunction "P$1_P$1") (pintype "passive"))
      (node (ref "C5") (pin "P$1") (pinfunction "P$1_P$1") (pintype "passive"))
      (node (ref "C6") (pin "P$1") (pinfunction "P$1_P$1") (pintype "passive"))
      (node (ref "C7") (pin "P$1") (pinfunction "P$1_P$1") (pintype "passive"))
      (node (ref "ISP") (pin "P$2") (pinfunction "PIN2_P$2") (pintype "bidirectional"))
      (node (ref "JP1") (pin "P$1") (pinfunction "P$1_P$1") (pintype "passive"))
      (node (ref "JP2") (pin "P$2") (pinfunction "P$2_P$2") (pintype "passive"))
      (node (ref "R1") (pin "P$1") (pinfunction "P$1_P$1") (pintype "passive"))
      (node (ref "TC1") (pin "P$2") (pinfunction "PIN2_P$2") (pintype "bidirectional"))
      (node (ref "U1") (pin "P$18") (pinfunction "AVCC_P$18") (pintype "power_in"))
      (node (ref "U1") (pin "P$4") (pinfunction "VCC_P$4") (pintype "power_in"))
      (node (ref "U1") (pin "P$6") (pinfunction "VCC_P$6") (pintype "power_in"))
    )
    (net (code "50") (name "VIN") (class "Default")
      (node (ref "C15") (pin "P$1") (pinfunction "P$1_P$1") (pintype "passive"))
      (node (ref "C18") (pin "P$1") (pinfunction "P$1_P$1") (pintype "passive"))
      (node (ref "POWER") (pin "P$6") (pinfunction "PIN6_P$6") (pintype "bidirectional"))
      (node (ref "PWR_IN") (pin "PIN") (pinfunction "PIN_PIN") (pintype "power_in"))
      (node (ref "U5") (pin "P$4") (pinfunction "VIN_P$4") (pintype "bidirectional"))
    )
    (net (code "51") (name "VIN_5.0V") (class "Default")
      (node (ref "C16") (pin "P$1") (pinfunction "P$1_P$1") (pintype "passive"))
      (node (ref "C17") (pin "P$1") (pinfunction "P$1_P$1") (pintype "passive"))
      (node (ref "U4") (pin "3") (pinfunction "VSNS_3") (pintype "bidirectional"))
      (node (ref "U4") (pin "8") (pinfunction "IN1_8") (pintype "bidirectional"))
      (node (ref "U5") (pin "P$1") (pinfunction "VOUT_P$1") (pintype "bidirectional"))
      (node (ref "U5") (pin "P$3") (pinfunction "VOUT_P$3") (pintype "bidirectional"))
    )
    (net (code "52") (name "unconnected-(J1-CC2-PadB5)") (class "Default")
      (node (ref "J1") (pin "B5") (pinfunction "CC2_B5") (pintype "bidirectional"))
    )
    (net (code "53") (name "unconnected-(J1-RX1+-PadB11)") (class "Default")
      (node (ref "J1") (pin "B11") (pinfunction "RX1+_B11") (pintype "bidirectional"))
    )
    (net (code "54") (name "unconnected-(J1-RX1--PadB10)") (class "Default")
      (node (ref "J1") (pin "B10") (pinfunction "RX1-_B10") (pintype "bidirectional"))
    )
    (net (code "55") (name "unconnected-(J1-RX2+-PadA11)") (class "Default")
      (node (ref "J1") (pin "A11") (pinfunction "RX2+_A11") (pintype "bidirectional"))
    )
    (net (code "56") (name "unconnected-(J1-RX2--PadA10)") (class "Default")
      (node (ref "J1") (pin "A10") (pinfunction "RX2-_A10") (pintype "bidirectional"))
    )
    (net (code "57") (name "unconnected-(J1-SBU1-PadA8)") (class "Default")
      (node (ref "J1") (pin "A8") (pinfunction "SBU1_A8") (pintype "bidirectional"))
    )
    (net (code "58") (name "unconnected-(J1-SBU2-PadB8)") (class "Default")
      (node (ref "J1") (pin "B8") (pinfunction "SBU2_B8") (pintype "bidirectional"))
    )
    (net (code "59") (name "unconnected-(J1-TX1+-PadA2)") (class "Default")
      (node (ref "J1") (pin "A2") (pinfunction "TX1+_A2") (pintype "bidirectional"))
    )
    (net (code "60") (name "unconnected-(J1-TX1--PadA3)") (class "Default")
      (node (ref "J1") (pin "A3") (pinfunction "TX1-_A3") (pintype "bidirectional"))
    )
    (net (code "61") (name "unconnected-(J1-TX2+-PadB2)") (class "Default")
      (node (ref "J1") (pin "B2") (pinfunction "TX2+_B2") (pintype "bidirectional"))
    )
    (net (code "62") (name "unconnected-(J1-TX2--PadB3)") (class "Default")
      (node (ref "J1") (pin "B3") (pinfunction "TX2-_B3") (pintype "bidirectional"))
    )
    (net (code "63") (name "unconnected-(RESET-PadP$2)") (class "Default")
      (node (ref "RESET") (pin "P$2") (pinfunction "P$2_P$2") (pintype "bidirectional"))
    )
    (net (code "64") (name "unconnected-(RESET-PadP$4)") (class "Default")
      (node (ref "RESET") (pin "P$4") (pinfunction "P$4_P$4") (pintype "bidirectional"))
    )
    (net (code "65") (name "unconnected-(U2-CBUS0-Pad12)") (class "Default")
      (node (ref "U2") (pin "12") (pinfunction "CBUS0_12") (pintype "bidirectional"))
    )
    (net (code "66") (name "unconnected-(U2-CBUS3-Pad14)") (class "Default")
      (node (ref "U2") (pin "14") (pinfunction "CBUS3_14") (pintype "bidirectional"))
    )
    (net (code "67") (name "unconnected-(U2-CTS#-Pad4)") (class "Default")
      (node (ref "U2") (pin "4") (pinfunction "CTS#_4") (pintype "bidirectional"))
    )
    (net (code "68") (name "unconnected-(U4-STAT-Pad1)") (class "Default")
      (node (ref "U4") (pin "1") (pinfunction "STAT_1") (pintype "bidirectional"))
    )
  )
)
